# MT-PowerDivider_V1_0_0.net
KiCad netlist of a schematic drawn in Altium Designer
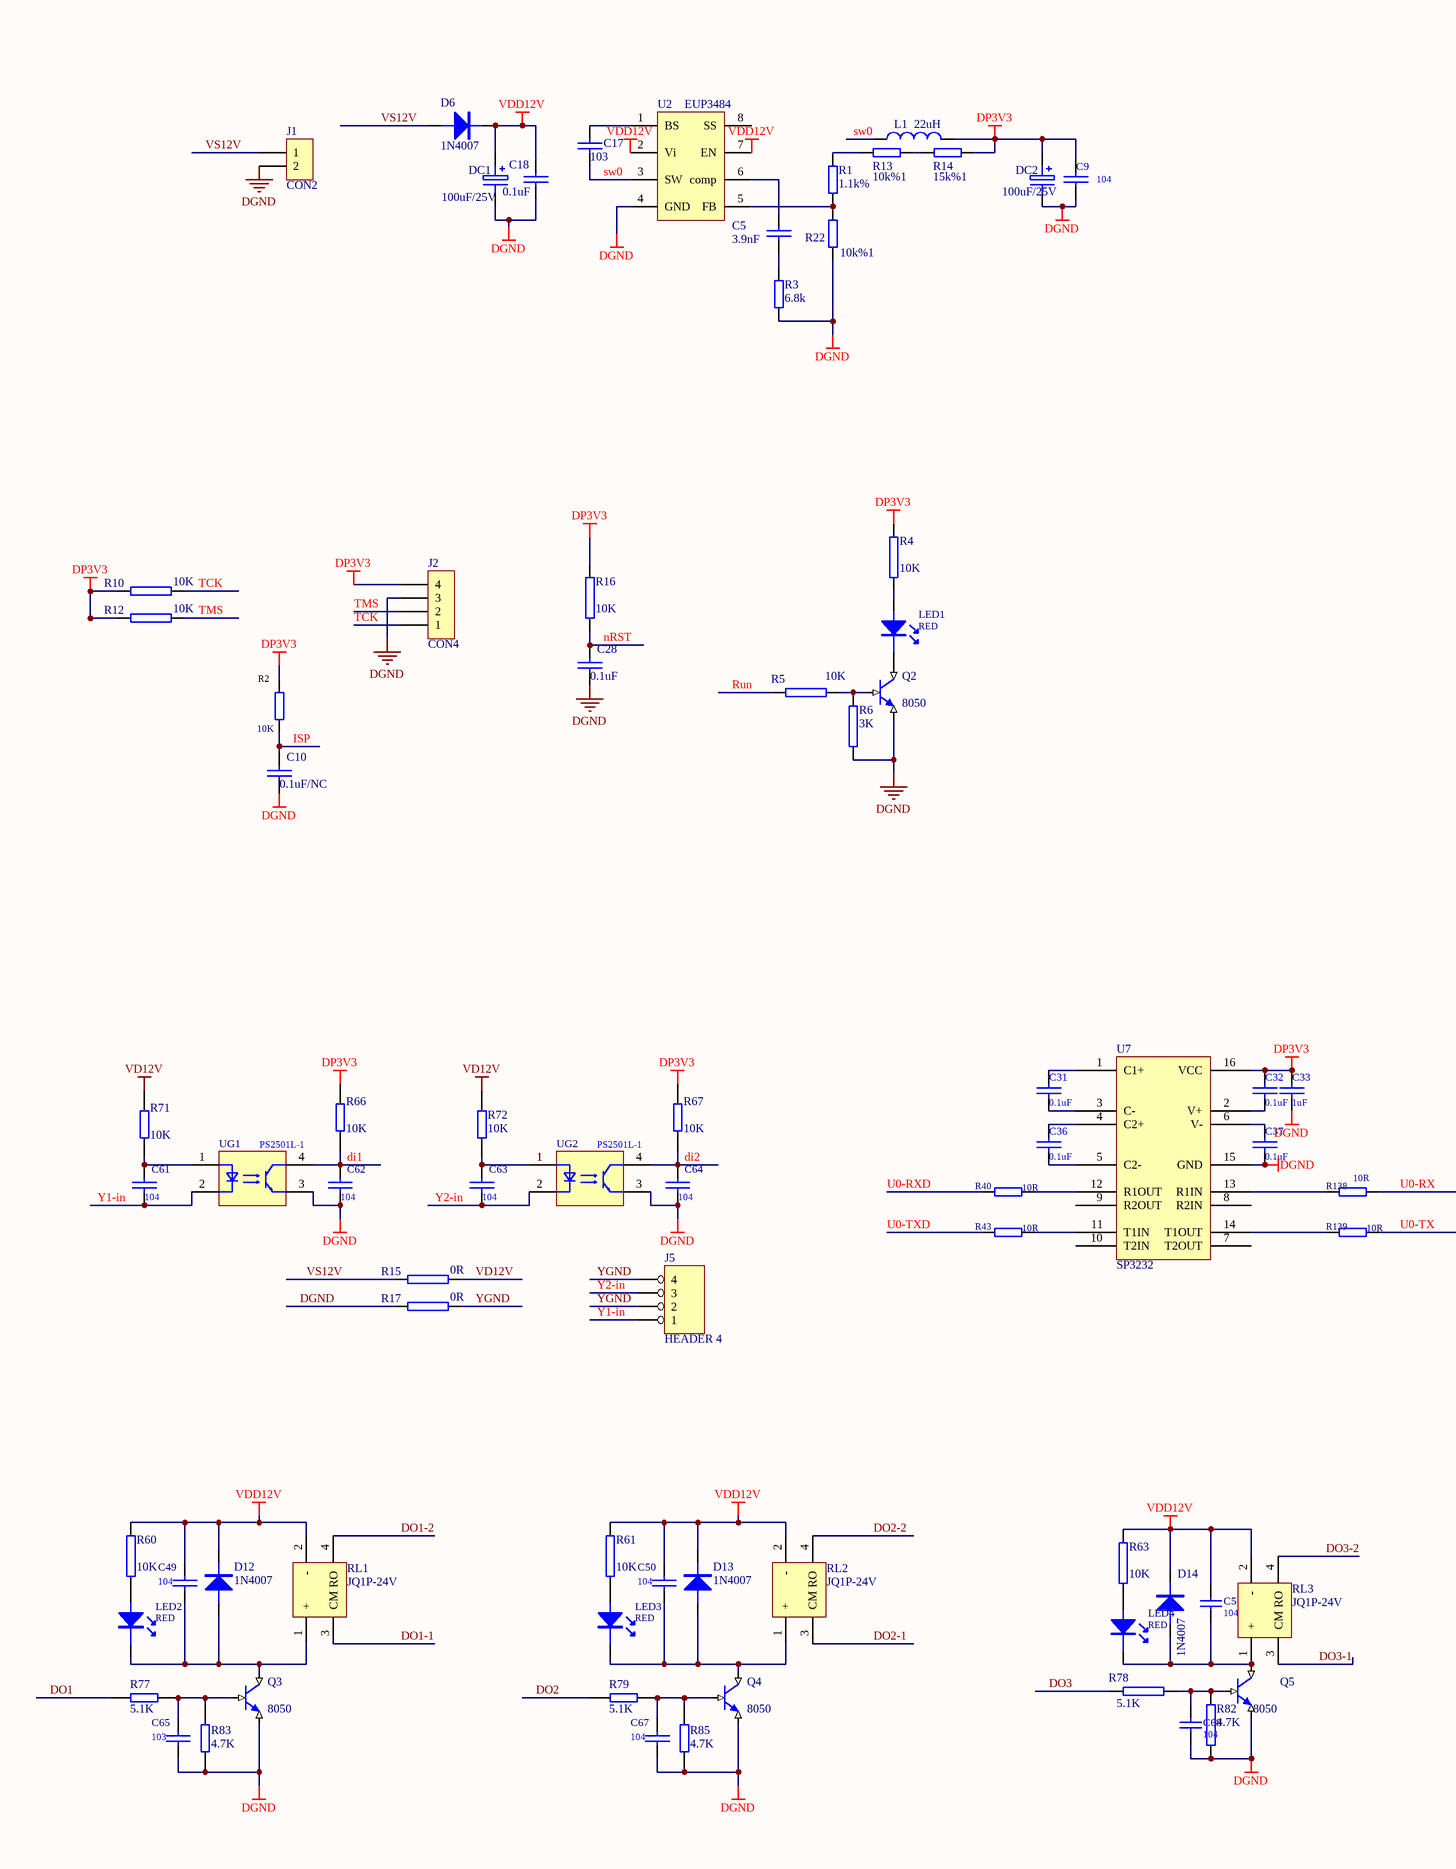
[diagram p0: MT-PowerDivider V1.0.0.SchDoc, left]
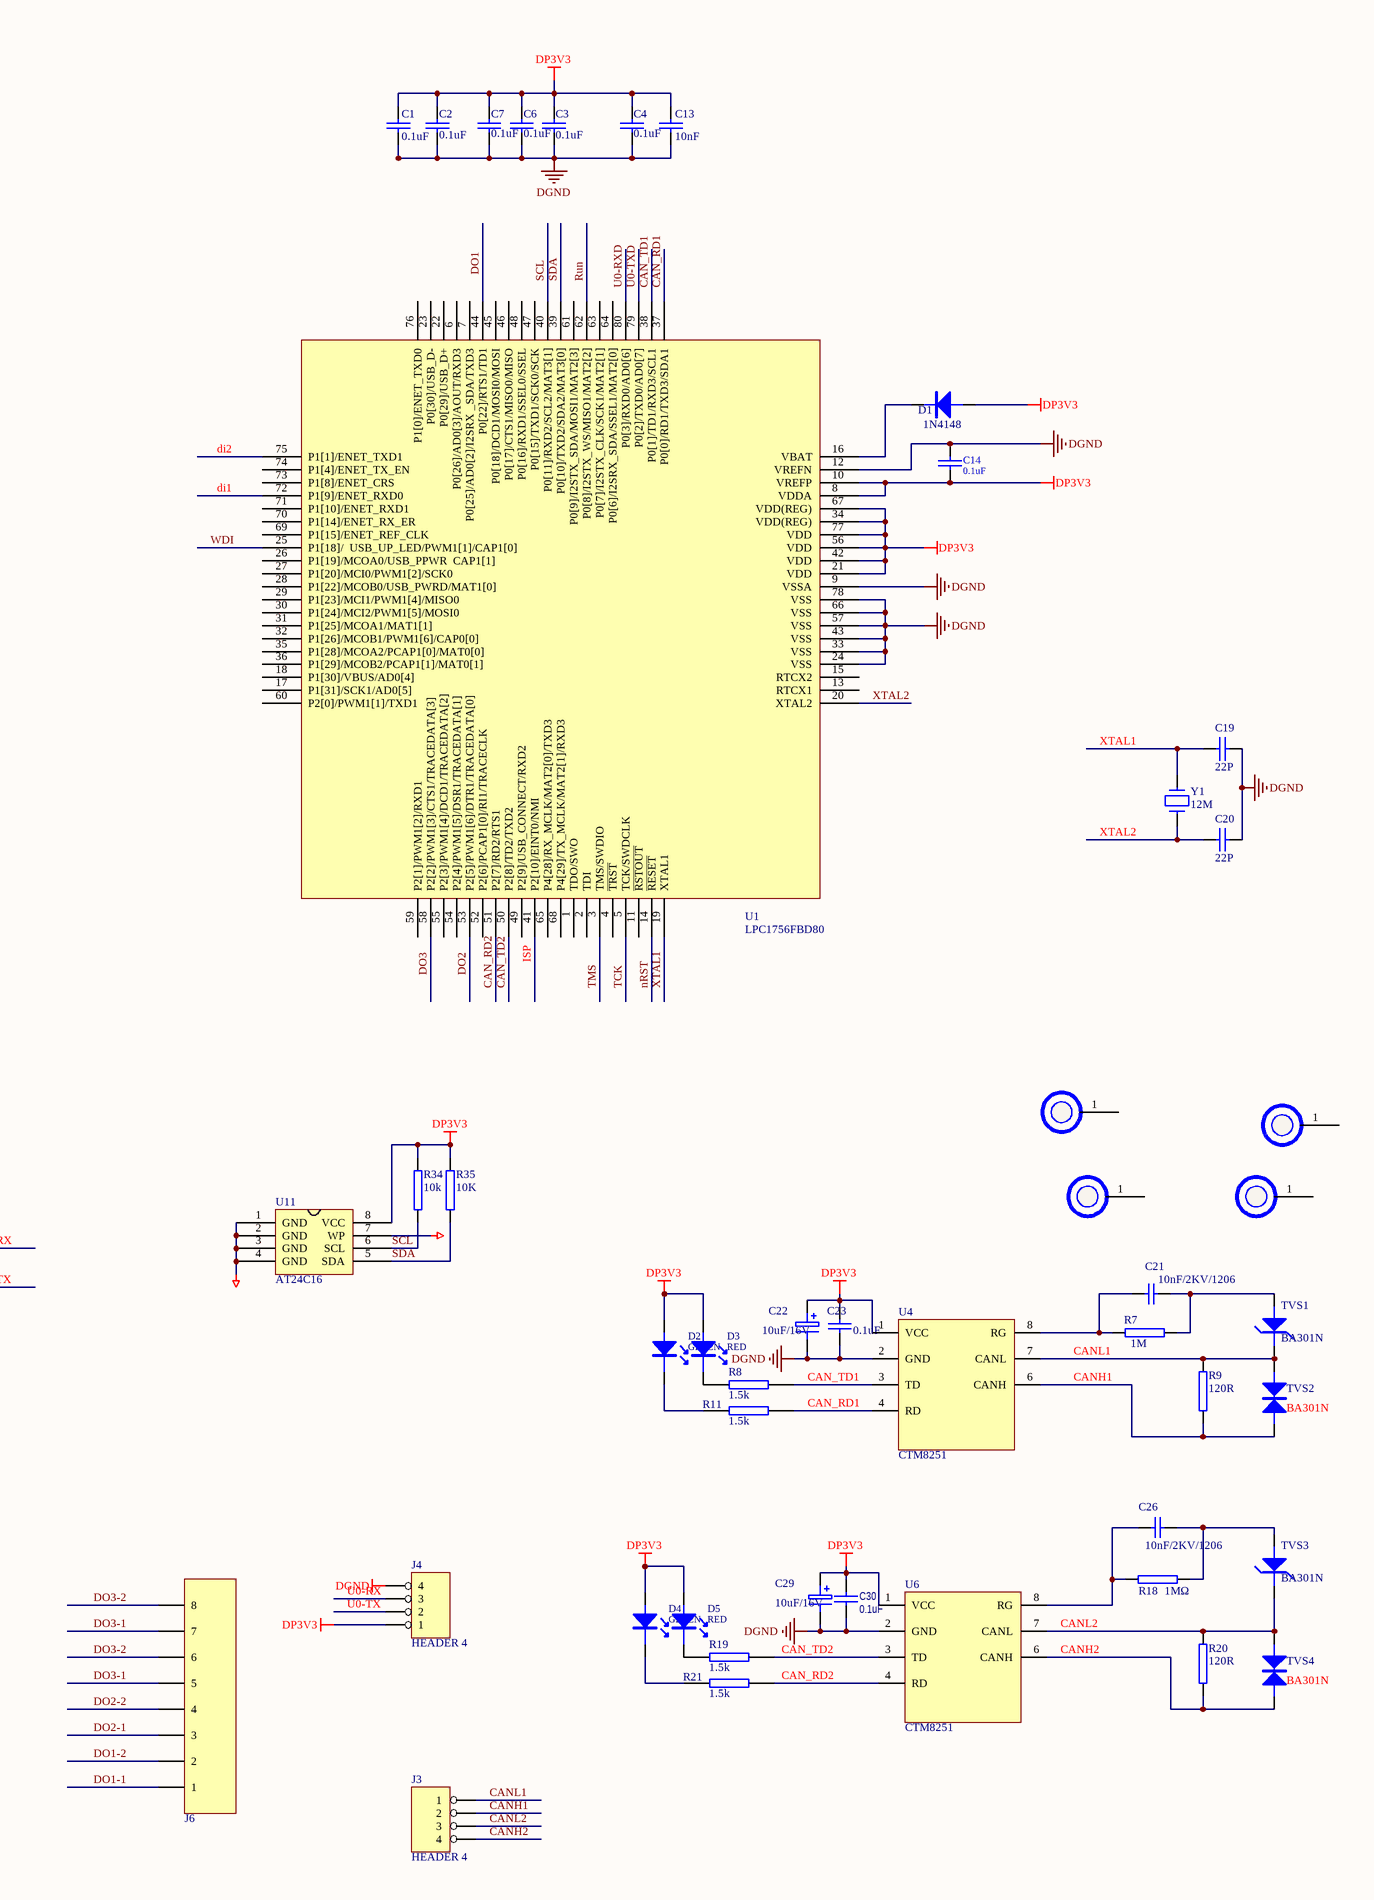
[diagram p1: MT-PowerDivider V1.0.0.SchDoc, right]

(export (version "E")
  (design (tool "Eeschema 10.0.6"))
  (components
    (comp (ref "5") (value "~") (footprint "HOLD-3.5MM") (libsource (lib "xiaodong") (part "HOLD_5X9MM")))
    (comp (ref "6") (value "~") (footprint "HOLD-3.5MM") (libsource (lib "xiaodong") (part "HOLD_5X9MM")))
    (comp (ref "7") (value "~") (footprint "HOLD-3.5MM") (libsource (lib "xiaodong") (part "HOLD_5X9MM")))
    (comp (ref "8") (value "~") (footprint "HOLD-3.5MM") (libsource (lib "xiaodong") (part "HOLD_5X9MM")))
    (comp (ref "C1") (value "0.1uF") (footprint "0603C") (libsource (lib "*") (part "CAP1")))
    (comp (ref "C2") (value "0.1uF") (footprint "0603C") (libsource (lib "*") (part "CAP1")))
    (comp (ref "C3") (value "0.1uF") (footprint "0603C") (libsource (lib "*") (part "CAP1")))
    (comp (ref "C4") (value "0.1uF") (footprint "0603C") (libsource (lib "*") (part "CAP1")))
    (comp (ref "C5") (value "3.9nF") (footprint "0603C") (libsource (lib "*") (part "CAP")))
    (comp (ref "C6") (value "0.1uF") (footprint "0603C") (libsource (lib "*") (part "CAP1")))
    (comp (ref "C7") (value "0.1uF") (footprint "0603C") (libsource (lib "*") (part "CAP1")))
    (comp (ref "C9")
      (value "104")
      (footprint "0603C")
      (description "Capacitor")
      (libsource (lib "*") (part "CAP"))
    )
    (comp (ref "C10")
      (value "0.1uF/NC")
      (footprint "0603C")
      (description "CAP")
      (libsource (lib "*") (part "CAP1"))
    )
    (comp (ref "C13") (value "10nF") (footprint "0603C") (libsource (lib "*") (part "CAP1")))
    (comp (ref "C14")
      (value "0.1uF")
      (footprint "0603C")
      (description "Capacitor")
      (libsource (lib "xiaodong") (part "CAP_3"))
    )
    (comp (ref "C17") (value "103") (footprint "0603C") (libsource (lib "*") (part "CAP")))
    (comp (ref "C18") (value "0.1uF") (footprint "0805C") (libsource (lib "*") (part "CAP")))
    (comp (ref "C19") (value "22P") (footprint "0603C") (libsource (lib "*") (part "CAP1")))
    (comp (ref "C20") (value "22P") (footprint "0603C") (libsource (lib "*") (part "CAP1")))
    (comp (ref "C21")
      (value "10nF/2KV/1206")
      (footprint "1206C")
      (description "C0603")
      (fields (field (name "PUBLISHER") "*"))
      (libsource (lib "*") (part "0.1uF"))
    )
    (comp (ref "C22") (value "10uF/16V") (footprint "CA1206") (libsource (lib "*") (part "CAP2")))
    (comp (ref "C23")
      (value "0.1uF")
      (footprint "0603C")
      (description "Capacitor")
      (libsource (lib "") (part "CAP_1"))
    )
    (comp (ref "C26")
      (value "10nF/2KV/1206")
      (footprint "1206C")
      (description "C0603")
      (fields (field (name "PUBLISHER") "*"))
      (libsource (lib "*") (part "0.1uF"))
    )
    (comp (ref "C28")
      (value "0.1uF")
      (footprint "0603C")
      (description "CAP")
      (libsource (lib "*") (part "CAP1"))
    )
    (comp (ref "C29") (value "10uF/16V") (footprint "CA1206") (libsource (lib "*") (part "CAP2")))
    (comp (ref "C30")
      (value "0.1uF")
      (footprint "0603C")
      (description "Capacitor")
      (libsource (lib "") (part "CAP_1"))
    )
    (comp (ref "C31")
      (value "0.1uF")
      (footprint "0603C")
      (description "Capacitor")
      (libsource (lib "*") (part "CAP"))
    )
    (comp (ref "C32")
      (value "0.1uF")
      (footprint "0603C")
      (description "Capacitor")
      (libsource (lib "*") (part "CAP"))
    )
    (comp (ref "C33")
      (value "1uF")
      (footprint "0603C")
      (description "Capacitor")
      (libsource (lib "*") (part "CAP"))
    )
    (comp (ref "C36")
      (value "0.1uF")
      (footprint "0603C")
      (description "Capacitor")
      (libsource (lib "*") (part "CAP"))
    )
    (comp (ref "C37")
      (value "0.1uF")
      (footprint "0603C")
      (description "Capacitor")
      (libsource (lib "*") (part "CAP"))
    )
    (comp (ref "C49")
      (value "104")
      (footprint "0603C")
      (description "Capacitor")
      (libsource (lib "*") (part "CAP"))
    )
    (comp (ref "C50")
      (value "104")
      (footprint "0603C")
      (description "Capacitor")
      (libsource (lib "*") (part "CAP"))
    )
    (comp (ref "C51")
      (value "104")
      (footprint "0603C")
      (description "Capacitor")
      (fields (field (name "PUBLISHER") "*"))
      (libsource (lib "*") (part "Cap"))
    )
    (comp (ref "C61")
      (value "104")
      (footprint "0603C")
      (description "Capacitor")
      (libsource (lib "*") (part "CAP"))
    )
    (comp (ref "C62")
      (value "104")
      (footprint "0603C")
      (description "Capacitor")
      (libsource (lib "*") (part "CAP"))
    )
    (comp (ref "C63")
      (value "104")
      (footprint "0603C")
      (description "Capacitor")
      (libsource (lib "*") (part "CAP"))
    )
    (comp (ref "C64")
      (value "104")
      (footprint "0603C")
      (description "Capacitor")
      (libsource (lib "*") (part "CAP"))
    )
    (comp (ref "C65")
      (value "103")
      (footprint "0603C")
      (description "Capacitor")
      (libsource (lib "*") (part "CAP"))
    )
    (comp (ref "C67")
      (value "104")
      (footprint "0603C")
      (description "Capacitor")
      (libsource (lib "*") (part "CAP"))
    )
    (comp (ref "C68")
      (value "104")
      (footprint "0603C")
      (description "Capacitor")
      (fields (field (name "PUBLISHER") "*"))
      (libsource (lib "*") (part "Cap"))
    )
    (comp (ref "D1") (value "1N4148") (footprint "1206D") (libsource (lib "*") (part "DIODE")))
    (comp (ref "D2") (value "GREEN") (footprint "D0805") (libsource (lib "*") (part "LED")))
    (comp (ref "D3") (value "RED") (footprint "D0805") (libsource (lib "*") (part "LED")))
    (comp (ref "D4") (value "GREEN") (footprint "D0805") (libsource (lib "*") (part "LED")))
    (comp (ref "D5") (value "RED") (footprint "D0805") (libsource (lib "*") (part "LED")))
    (comp (ref "D6") (value "1N4007") (footprint "1206D") (libsource (lib "ucharge06011415") (part "DIODE")))
    (comp (ref "D12") (value "1N4007") (footprint "1206D") (libsource (lib "*") (part "DIODE")))
    (comp (ref "D13") (value "1N4007") (footprint "1206D") (libsource (lib "*") (part "DIODE")))
    (comp (ref "D14") (value "1N4007") (footprint "1206D") (libsource (lib "*") (part "DIODE")))
    (comp (ref "DC1") (value "100uF/25V") (footprint "C100UF16VEJ") (libsource (lib "*") (part "CAP2")))
    (comp (ref "DC2") (value "100uF/25V") (footprint "C100UF16VEJ") (libsource (lib "*") (part "CAP2")))
    (comp (ref "J1")
      (value "CON2")
      (footprint "KF2EDG-2P=3.81mm")
      (libsource (lib "ucharge06011415") (part "CON2"))
    )
    (comp (ref "J2")
      (value "CON4")
      (footprint "COM4-2.54mm-90")
      (description "Connector")
      (libsource (lib "Mini9") (part "CON4"))
    )
    (comp (ref "J3")
      (value "HEADER 4")
      (footprint "KF2EDG-4P-3.81mm")
      (description "4 Pin Header")
      (libsource (lib "") (part "4 HEADER_1"))
    )
    (comp (ref "J4")
      (value "HEADER 4")
      (footprint "KF2EDG-4P-3.81mm")
      (description "4 Pin Header")
      (libsource (lib "ueee20160531") (part "4 HEADER"))
    )
    (comp (ref "J5")
      (value "HEADER 4")
      (footprint "KF2EDG-4P-3.81mm")
      (description "4 Pin Header")
      (libsource (lib "ueee20160531") (part "4 HEADER"))
    )
    (comp (ref "J6") (value "CON8") (footprint "KF2EDG-8P-3.81mm") (libsource (lib "MT") (part "CON8")))
    (comp (ref "L1") (value "22uH") (footprint "LC7*7*3_L") (libsource (lib "*") (part "INDUCTOR")))
    (comp (ref "LED1") (value "RED") (footprint "D0805") (libsource (lib "*") (part "LED")))
    (comp (ref "LED2") (value "RED") (footprint "D0805") (libsource (lib "*") (part "LED")))
    (comp (ref "LED3") (value "RED") (footprint "D0805") (libsource (lib "*") (part "LED")))
    (comp (ref "LED4") (value "RED") (footprint "D0805") (libsource (lib "*") (part "LED")))
    (comp (ref "Q2") (value "8050") (footprint "SOT23") (libsource (lib "*") (part "NPN")))
    (comp (ref "Q3") (value "8050") (footprint "SOT23") (libsource (lib "*") (part "NPN")))
    (comp (ref "Q4") (value "8050") (footprint "SOT23") (libsource (lib "*") (part "NPN")))
    (comp (ref "Q5") (value "8050") (footprint "SOT23") (libsource (lib "*") (part "NPN")))
    (comp (ref "R1") (value "1.1k%") (footprint "0603R") (libsource (lib "*") (part "R_S")))
    (comp (ref "R2")
      (value "10K")
      (footprint "0603R")
      (description "RES")
      (libsource (lib "*") (part "RES-1"))
    )
    (comp (ref "R3") (value "6.8k") (footprint "0603R") (libsource (lib "*") (part "R_S")))
    (comp (ref "R4") (value "10K") (footprint "0603R") (libsource (lib "*") (part "RES1")))
    (comp (ref "R5") (value "10K") (footprint "0603R") (libsource (lib "*") (part "RES1")))
    (comp (ref "R6") (value "3K") (footprint "0603R") (libsource (lib "*") (part "RES1")))
    (comp (ref "R7") (value "1M") (footprint "1206R") (libsource (lib "") (part "RES2_1")))
    (comp (ref "R8") (value "1.5k") (footprint "0603R") (libsource (lib "*") (part "RES2")))
    (comp (ref "R9") (value "120R") (footprint "1206R") (libsource (lib "") (part "RES2_1")))
    (comp (ref "R10") (value "10K") (footprint "0603R") (libsource (lib "*") (part "RES1")))
    (comp (ref "R11") (value "1.5k") (footprint "0603R") (libsource (lib "*") (part "RES2")))
    (comp (ref "R12") (value "10K") (footprint "0603R") (libsource (lib "*") (part "RES1")))
    (comp (ref "R13") (value "10k%1") (footprint "0603R") (libsource (lib "*") (part "R_S")))
    (comp (ref "R14") (value "15k%1") (footprint "0603R") (libsource (lib "*") (part "R_S")))
    (comp (ref "R15") (value "0R") (footprint "0603R") (libsource (lib "*") (part "RES1")))
    (comp (ref "R16") (value "10K") (footprint "0603R") (libsource (lib "*") (part "RES1")))
    (comp (ref "R17") (value "0R") (footprint "0603R") (libsource (lib "*") (part "RES1")))
    (comp (ref "R18")
      (value "1MΩ")
      (footprint "1206R")
      (fields (field (name "Comment") "1M"))
      (libsource (lib "") (part "RES2_1"))
    )
    (comp (ref "R19") (value "1.5k") (footprint "0603R") (libsource (lib "*") (part "RES2")))
    (comp (ref "R20") (value "120R") (footprint "1206R") (libsource (lib "") (part "RES2_1")))
    (comp (ref "R21") (value "1.5k") (footprint "0603R") (libsource (lib "*") (part "RES2")))
    (comp (ref "R22") (value "10k%1") (footprint "0603R") (libsource (lib "*") (part "R_S")))
    (comp (ref "R34")
      (value "10k")
      (footprint "0603R")
      (description "0603贴片电阻/10K/0.1W/±5%")
      (libsource (lib "") (part "RES1_2"))
    )
    (comp (ref "R35")
      (value "10K")
      (footprint "0603R")
      (description "0603贴片电阻/10K/0.1W/±5%")
      (libsource (lib "") (part "RES1_2"))
    )
    (comp (ref "R40")
      (value "10R")
      (footprint "0603R")
      (description "RES")
      (libsource (lib "*") (part "RES-1"))
    )
    (comp (ref "R43")
      (value "10R")
      (footprint "0603R")
      (description "RES")
      (libsource (lib "*") (part "RES-1"))
    )
    (comp (ref "R60") (value "10K") (footprint "0603R") (libsource (lib "*") (part "RES1")))
    (comp (ref "R61") (value "10K") (footprint "0603R") (libsource (lib "*") (part "RES1")))
    (comp (ref "R63") (value "10K") (footprint "0603R") (libsource (lib "*") (part "RES1")))
    (comp (ref "R66") (value "10K") (footprint "0603R") (libsource (lib "") (part "RES1_1")))
    (comp (ref "R67") (value "10K") (footprint "0603R") (libsource (lib "") (part "RES1_1")))
    (comp (ref "R71") (value "10K") (footprint "0603R") (libsource (lib "") (part "RES1_1")))
    (comp (ref "R72") (value "10K") (footprint "0603R") (libsource (lib "") (part "RES1_1")))
    (comp (ref "R77") (value "5.1K") (footprint "0603R") (libsource (lib "") (part "RES1_1")))
    (comp (ref "R78") (value "5.1K") (footprint "0603R") (libsource (lib "*") (part "RES1")))
    (comp (ref "R79") (value "5.1K") (footprint "0603R") (libsource (lib "") (part "RES1_1")))
    (comp (ref "R82") (value "4.7K") (footprint "0603R") (libsource (lib "*") (part "RES1")))
    (comp (ref "R83") (value "4.7K") (footprint "0603R") (libsource (lib "") (part "RES1_1")))
    (comp (ref "R85") (value "4.7K") (footprint "0603R") (libsource (lib "") (part "RES1_1")))
    (comp (ref "R138")
      (value "10R")
      (footprint "0603R")
      (description "RES")
      (libsource (lib "*") (part "RES-1"))
    )
    (comp (ref "R139")
      (value "10R")
      (footprint "0603R")
      (description "RES")
      (libsource (lib "*") (part "RES-1"))
    )
    (comp (ref "RL1")
      (value "JQ1P-24V")
      (footprint "HF32F-12V")
      (libsource (lib "UEEE20160408") (part "JQ1P-12V"))
    )
    (comp (ref "RL2")
      (value "JQ1P-24V")
      (footprint "HF32F-12V")
      (libsource (lib "UEEE20160408") (part "JQ1P-12V"))
    )
    (comp (ref "RL3")
      (value "JQ1P-24V")
      (footprint "HF32F-12V")
      (libsource (lib "UEEE20160408") (part "JQ1P-12V"))
    )
    (comp (ref "TVS1") (value "BA301N") (footprint "3528TVS") (libsource (lib "*") (part "TVS-D")))
    (comp (ref "TVS2") (value "BA301N") (footprint "3528TVS") (libsource (lib "*") (part "TVS")))
    (comp (ref "TVS3") (value "BA301N") (footprint "3528TVS") (libsource (lib "*") (part "TVS-D")))
    (comp (ref "TVS4") (value "BA301N") (footprint "3528TVS") (libsource (lib "*") (part "TVS")))
    (comp (ref "U1")
      (value "LPC1756FBD80")
      (footprint "LQFP-80")
      (description "LPC1756FBD80,LQFP-80_12x12x05P,NXP")
      (libsource (lib "xiaodong") (part "LPC1756FBD80"))
    )
    (comp (ref "U2") (value "EUP3484") (footprint "SOP8") (libsource (lib "*") (part "EUP3484")))
    (comp (ref "U4") (value "CTM8251") (footprint "CTM8251KT") (libsource (lib "直流原理图库") (part "CTM8251")))
    (comp (ref "U6") (value "CTM8251") (footprint "CTM8251KT") (libsource (lib "直流原理图库") (part "CTM8251")))
    (comp (ref "U7") (value "SP3232") (footprint "SO-16") (libsource (lib "*") (part "MAX232ESE")))
    (comp (ref "U11")
      (value "AT24C16")
      (footprint "SOP8")
      (description "EEPROM/64K/2.7V/SOP8/ATMEL")
      (libsource (lib "*") (part "AT24C64"))
    )
    (comp (ref "UG1") (value "PS2501L-1") (footprint "DIP-4") (libsource (lib "*") (part "PS2501-1")))
    (comp (ref "UG2") (value "PS2501L-1") (footprint "DIP-4") (libsource (lib "*") (part "PS2501-1")))
    (comp (ref "Y1") (value "12M") (footprint "ZS_SMD") (libsource (lib "*") (part "CRYSTAL")))
  )
  (nets
    (net (code "1") (name "/CANH1") (class "Default")
      (node (ref "J3") (pin "2") (pinfunction "2_2") (pintype "passive"))
      (node (ref "R9") (pin "2") (pinfunction "2_2") (pintype "passive"))
      (node (ref "TVS2") (pin "1") (pintype "passive"))
      (node (ref "U4") (pin "6") (pinfunction "CANH_6") (pintype "passive"))
    )
    (net (code "2") (name "/CANH2") (class "Default")
      (node (ref "J3") (pin "4") (pinfunction "4_4") (pintype "passive"))
      (node (ref "R20") (pin "2") (pinfunction "2_2") (pintype "passive"))
      (node (ref "TVS4") (pin "1") (pintype "passive"))
      (node (ref "U6") (pin "6") (pinfunction "CANH_6") (pintype "passive"))
    )
    (net (code "3") (name "/CANL1") (class "Default")
      (node (ref "J3") (pin "1") (pinfunction "1_1") (pintype "passive"))
      (node (ref "R9") (pin "1") (pinfunction "1_1") (pintype "passive"))
      (node (ref "TVS1") (pin "2") (pintype "passive"))
      (node (ref "TVS2") (pin "2") (pintype "passive"))
      (node (ref "U4") (pin "7") (pinfunction "CANL_7") (pintype "passive"))
    )
    (net (code "4") (name "/CANL2") (class "Default")
      (node (ref "J3") (pin "3") (pinfunction "3_3") (pintype "passive"))
      (node (ref "R20") (pin "1") (pinfunction "1_1") (pintype "passive"))
      (node (ref "TVS3") (pin "2") (pintype "passive"))
      (node (ref "TVS4") (pin "2") (pintype "passive"))
      (node (ref "U6") (pin "7") (pinfunction "CANL_7") (pintype "passive"))
    )
    (net (code "5") (name "/CAN_RD1") (class "Default")
      (node (ref "R11") (pin "2") (pinfunction "2_2") (pintype "passive"))
      (node (ref "U1") (pin "37") (pinfunction "P0[0]/RD1/TXD3/SDA1_37") (pintype "passive"))
      (node (ref "U4") (pin "4") (pinfunction "RD_4") (pintype "passive"))
    )
    (net (code "6") (name "/CAN_RD2") (class "Default")
      (node (ref "R21") (pin "2") (pinfunction "2_2") (pintype "passive"))
      (node (ref "U1") (pin "51") (pinfunction "P2[7]/RD2/RTS1_51") (pintype "passive"))
      (node (ref "U6") (pin "4") (pinfunction "RD_4") (pintype "passive"))
    )
    (net (code "7") (name "/CAN_TD1") (class "Default")
      (node (ref "R8") (pin "2") (pinfunction "2_2") (pintype "passive"))
      (node (ref "U1") (pin "38") (pinfunction "P0[1]/TD1/RXD3/SCL1_38") (pintype "passive"))
      (node (ref "U4") (pin "3") (pinfunction "TD_3") (pintype "passive"))
    )
    (net (code "8") (name "/CAN_TD2") (class "Default")
      (node (ref "R19") (pin "2") (pinfunction "2_2") (pintype "passive"))
      (node (ref "U1") (pin "50") (pinfunction "P2[8]/TD2/TXD2_50") (pintype "passive"))
      (node (ref "U6") (pin "3") (pinfunction "TD_3") (pintype "passive"))
    )
    (net (code "9") (name "/DO1") (class "Default")
      (node (ref "R77") (pin "1") (pinfunction "1_1") (pintype "passive"))
      (node (ref "U1") (pin "44") (pinfunction "P0[22]/RTS1/TD1_44") (pintype "passive"))
    )
    (net (code "10") (name "/DO1-1") (class "Default")
      (node (ref "J6") (pin "1") (pinfunction "1_1") (pintype "passive"))
      (node (ref "RL1") (pin "3") (pinfunction "CM_3") (pintype "passive"))
    )
    (net (code "11") (name "/DO1-2") (class "Default")
      (node (ref "J6") (pin "2") (pinfunction "2_2") (pintype "passive"))
      (node (ref "RL1") (pin "4") (pinfunction "RO_4") (pintype "passive"))
    )
    (net (code "12") (name "/DO2") (class "Default")
      (node (ref "R79") (pin "1") (pinfunction "1_1") (pintype "passive"))
      (node (ref "U1") (pin "53") (pinfunction "P2[5]/PWM1[6]/DTR1/TRACEDATA[0]_53") (pintype "passive"))
    )
    (net (code "13") (name "/DO2-1") (class "Default")
      (node (ref "J6") (pin "3") (pinfunction "3_3") (pintype "passive"))
      (node (ref "RL2") (pin "3") (pinfunction "CM_3") (pintype "passive"))
    )
    (net (code "14") (name "/DO2-2") (class "Default")
      (node (ref "J6") (pin "4") (pinfunction "4_4") (pintype "passive"))
      (node (ref "RL2") (pin "4") (pinfunction "RO_4") (pintype "passive"))
    )
    (net (code "15") (name "/DO3") (class "Default")
      (node (ref "R78") (pin "1") (pinfunction "1_1") (pintype "passive"))
      (node (ref "U1") (pin "58") (pinfunction "P2[2]/PWM1[3]/CTS1/TRACEDATA[3]_58") (pintype "passive"))
    )
    (net (code "16") (name "/DO3-1") (class "Default")
      (node (ref "J6") (pin "5") (pinfunction "5_5") (pintype "passive"))
      (node (ref "J6") (pin "7") (pinfunction "7_7") (pintype "passive"))
      (node (ref "RL3") (pin "3") (pinfunction "CM_3") (pintype "passive"))
    )
    (net (code "17") (name "/DO3-2") (class "Default")
      (node (ref "J6") (pin "6") (pinfunction "6_6") (pintype "passive"))
      (node (ref "J6") (pin "8") (pinfunction "8_8") (pintype "passive"))
      (node (ref "RL3") (pin "4") (pinfunction "RO_4") (pintype "passive"))
    )
    (net (code "18") (name "/ISP") (class "Default")
      (node (ref "C10") (pin "2") (pinfunction "2_2") (pintype "passive"))
      (node (ref "R2") (pin "1") (pintype "passive"))
      (node (ref "U1") (pin "41") (pinfunction "P2[10]/EINT0/NMI_41") (pintype "passive"))
    )
    (net (code "19") (name "/Run") (class "Default")
      (node (ref "R5") (pin "1") (pinfunction "1_1") (pintype "passive"))
      (node (ref "U1") (pin "62") (pinfunction "P0[8]/I2STX_WS/MISO1/MAT2[2]_62") (pintype "passive"))
    )
    (net (code "20") (name "/SCL") (class "Default")
      (node (ref "R34") (pin "2") (pinfunction "2_2") (pintype "passive"))
      (node (ref "U1") (pin "40") (pinfunction "P0[11]/RXD2/SCL2/MAT3[1]_40") (pintype "passive"))
      (node (ref "U11") (pin "6") (pinfunction "SCL_6") (pintype "passive"))
    )
    (net (code "21") (name "/SDA") (class "Default")
      (node (ref "R35") (pin "2") (pinfunction "2_2") (pintype "passive"))
      (node (ref "U1") (pin "39") (pinfunction "P0[10]/TXD2/SDA2/MAT3[0]_39") (pintype "passive"))
      (node (ref "U11") (pin "5") (pinfunction "SDA_5") (pintype "passive"))
    )
    (net (code "22") (name "/TCK") (class "Default")
      (node (ref "J2") (pin "1") (pinfunction "1_1") (pintype "passive"))
      (node (ref "R10") (pin "1") (pinfunction "1_1") (pintype "passive"))
      (node (ref "U1") (pin "5") (pinfunction "TCK/SWDCLK_5") (pintype "passive"))
    )
    (net (code "23") (name "/TMS") (class "Default")
      (node (ref "J2") (pin "2") (pinfunction "2_2") (pintype "passive"))
      (node (ref "R12") (pin "1") (pinfunction "1_1") (pintype "passive"))
      (node (ref "U1") (pin "3") (pinfunction "TMS/SWDIO_3") (pintype "passive"))
    )
    (net (code "24") (name "/U0-RX") (class "Default")
      (node (ref "J4") (pin "3") (pinfunction "3_3") (pintype "passive"))
      (node (ref "R138") (pin "2") (pintype "passive"))
    )
    (net (code "25") (name "/U0-RXD") (class "Default")
      (node (ref "R40") (pin "1") (pintype "passive"))
      (node (ref "U1") (pin "80") (pinfunction "P0[3]/RXD0/AD0[6]_80") (pintype "passive"))
    )
    (net (code "26") (name "/U0-TX") (class "Default")
      (node (ref "J4") (pin "2") (pinfunction "2_2") (pintype "passive"))
      (node (ref "R139") (pin "2") (pintype "passive"))
    )
    (net (code "27") (name "/U0-TXD") (class "Default")
      (node (ref "R43") (pin "1") (pintype "passive"))
      (node (ref "U1") (pin "79") (pinfunction "P0[2]/TXD0/AD0[7]_79") (pintype "passive"))
    )
    (net (code "28") (name "/VS12V") (class "Default")
      (node (ref "D6") (pin "1") (pinfunction "A_1") (pintype "passive"))
      (node (ref "J1") (pin "1") (pinfunction "1_1") (pintype "passive"))
      (node (ref "R15") (pin "2") (pinfunction "2_2") (pintype "passive"))
    )
    (net (code "29") (name "/WDI") (class "Default")
      (node (ref "U1") (pin "25") (pinfunction "P1[18]/__USB_UP_LED/PWM1[1]/CAP1[0]_25") (pintype "passive"))
    )
    (net (code "30") (name "/XTAL1") (class "Default")
      (node (ref "C19") (pin "1") (pinfunction "1_1") (pintype "passive"))
      (node (ref "U1") (pin "19") (pinfunction "XTAL1_19") (pintype "passive"))
      (node (ref "Y1") (pin "2") (pinfunction "2_2") (pintype "passive"))
    )
    (net (code "31") (name "/XTAL2") (class "Default")
      (node (ref "C20") (pin "1") (pinfunction "1_1") (pintype "passive"))
      (node (ref "U1") (pin "20") (pinfunction "XTAL2_20") (pintype "passive"))
      (node (ref "Y1") (pin "1") (pinfunction "1_1") (pintype "passive"))
    )
    (net (code "32") (name "/Y1-in") (class "Default")
      (node (ref "C61") (pin "2") (pintype "passive"))
      (node (ref "J5") (pin "1") (pinfunction "1_1") (pintype "passive"))
      (node (ref "UG1") (pin "2") (pintype "passive"))
    )
    (net (code "33") (name "/Y2-in") (class "Default")
      (node (ref "C63") (pin "2") (pintype "passive"))
      (node (ref "J5") (pin "3") (pinfunction "3_3") (pintype "passive"))
      (node (ref "UG2") (pin "2") (pintype "passive"))
    )
    (net (code "34") (name "/YGND") (class "Default")
      (node (ref "J5") (pin "2") (pinfunction "2_2") (pintype "passive"))
      (node (ref "J5") (pin "4") (pinfunction "4_4") (pintype "passive"))
      (node (ref "R17") (pin "1") (pinfunction "1_1") (pintype "passive"))
    )
    (net (code "35") (name "/di1") (class "Default")
      (node (ref "C62") (pin "1") (pintype "passive"))
      (node (ref "R66") (pin "2") (pinfunction "2_2") (pintype "passive"))
      (node (ref "U1") (pin "72") (pinfunction "P1[9]/ENET_RXD0_72") (pintype "passive"))
      (node (ref "UG1") (pin "4") (pintype "passive"))
    )
    (net (code "36") (name "/di2") (class "Default")
      (node (ref "C64") (pin "1") (pintype "passive"))
      (node (ref "R67") (pin "2") (pinfunction "2_2") (pintype "passive"))
      (node (ref "U1") (pin "75") (pinfunction "P1[1]/ENET_TXD1_75") (pintype "passive"))
      (node (ref "UG2") (pin "4") (pintype "passive"))
    )
    (net (code "37") (name "/nRST") (class "Default")
      (node (ref "C28") (pin "2") (pinfunction "2_2") (pintype "passive"))
      (node (ref "R16") (pin "2") (pinfunction "2_2") (pintype "passive"))
      (node (ref "U1") (pin "14") (pinfunction "~{RESET}_14") (pintype "passive"))
    )
    (net (code "38") (name "/sw0") (class "Default")
      (node (ref "C17") (pin "1") (pintype "passive"))
      (node (ref "L1") (pin "1") (pinfunction "1_1") (pintype "passive"))
      (node (ref "U2") (pin "3") (pinfunction "SW_3") (pintype "passive"))
    )
    (net (code "39") (name "DGND") (class "Default")
      (node (ref "C1") (pin "2") (pinfunction "2_2") (pintype "passive"))
      (node (ref "C10") (pin "1") (pinfunction "1_1") (pintype "passive"))
      (node (ref "C13") (pin "2") (pinfunction "2_2") (pintype "passive"))
      (node (ref "C14") (pin "1") (pintype "passive"))
      (node (ref "C18") (pin "1") (pintype "passive"))
      (node (ref "C19") (pin "2") (pinfunction "2_2") (pintype "passive"))
      (node (ref "C2") (pin "2") (pinfunction "2_2") (pintype "passive"))
      (node (ref "C20") (pin "2") (pinfunction "2_2") (pintype "passive"))
      (node (ref "C22") (pin "2") (pinfunction "2_2") (pintype "passive"))
      (node (ref "C23") (pin "2") (pinfunction "2_2") (pintype "passive"))
      (node (ref "C28") (pin "1") (pinfunction "1_1") (pintype "passive"))
      (node (ref "C29") (pin "2") (pinfunction "2_2") (pintype "passive"))
      (node (ref "C3") (pin "2") (pinfunction "2_2") (pintype "passive"))
      (node (ref "C30") (pin "1") (pinfunction "1_1") (pintype "passive"))
      (node (ref "C33") (pin "1") (pintype "passive"))
      (node (ref "C37") (pin "1") (pintype "passive"))
      (node (ref "C4") (pin "2") (pinfunction "2_2") (pintype "passive"))
      (node (ref "C6") (pin "2") (pinfunction "2_2") (pintype "passive"))
      (node (ref "C62") (pin "2") (pintype "passive"))
      (node (ref "C64") (pin "2") (pintype "passive"))
      (node (ref "C65") (pin "2") (pintype "passive"))
      (node (ref "C67") (pin "2") (pintype "passive"))
      (node (ref "C68") (pin "1") (pinfunction "1_1") (pintype "passive"))
      (node (ref "C7") (pin "2") (pinfunction "2_2") (pintype "passive"))
      (node (ref "C9") (pin "1") (pintype "passive"))
      (node (ref "DC1") (pin "2") (pinfunction "2_2") (pintype "passive"))
      (node (ref "DC2") (pin "2") (pinfunction "2_2") (pintype "passive"))
      (node (ref "J1") (pin "2") (pinfunction "2_2") (pintype "passive"))
      (node (ref "J2") (pin "3") (pinfunction "3_3") (pintype "passive"))
      (node (ref "J4") (pin "4") (pinfunction "4_4") (pintype "passive"))
      (node (ref "Q2") (pin "3") (pinfunction "E_3") (pintype "input"))
      (node (ref "Q3") (pin "3") (pinfunction "E_3") (pintype "input"))
      (node (ref "Q4") (pin "3") (pinfunction "E_3") (pintype "input"))
      (node (ref "Q5") (pin "3") (pinfunction "E_3") (pintype "input"))
      (node (ref "R17") (pin "2") (pinfunction "2_2") (pintype "passive"))
      (node (ref "R22") (pin "2") (pintype "passive"))
      (node (ref "R3") (pin "2") (pintype "passive"))
      (node (ref "R6") (pin "1") (pinfunction "1_1") (pintype "passive"))
      (node (ref "R82") (pin "1") (pinfunction "1_1") (pintype "passive"))
      (node (ref "R83") (pin "1") (pinfunction "1_1") (pintype "passive"))
      (node (ref "R85") (pin "1") (pinfunction "1_1") (pintype "passive"))
      (node (ref "U1") (pin "12") (pinfunction "VREFN_12") (pintype "passive"))
      (node (ref "U1") (pin "24") (pinfunction "VSS_24") (pintype "passive"))
      (node (ref "U1") (pin "33") (pinfunction "VSS_33") (pintype "passive"))
      (node (ref "U1") (pin "43") (pinfunction "VSS_43") (pintype "passive"))
      (node (ref "U1") (pin "57") (pinfunction "VSS_57") (pintype "passive"))
      (node (ref "U1") (pin "66") (pinfunction "VSS_66") (pintype "passive"))
      (node (ref "U1") (pin "78") (pinfunction "VSS_78") (pintype "passive"))
      (node (ref "U1") (pin "9") (pinfunction "VSSA_9") (pintype "passive"))
      (node (ref "U11") (pin "1") (pinfunction "GND_1") (pintype "passive"))
      (node (ref "U11") (pin "2") (pinfunction "GND_2") (pintype "passive"))
      (node (ref "U11") (pin "3") (pinfunction "GND_3") (pintype "passive"))
      (node (ref "U11") (pin "4") (pinfunction "GND_4") (pintype "passive"))
      (node (ref "U11") (pin "7") (pinfunction "WP_7") (pintype "passive"))
      (node (ref "U2") (pin "4") (pinfunction "GND_4") (pintype "passive"))
      (node (ref "U4") (pin "2") (pinfunction "GND_2") (pintype "passive"))
      (node (ref "U6") (pin "2") (pinfunction "GND_2") (pintype "passive"))
      (node (ref "U7") (pin "15") (pinfunction "GND_15") (pintype "passive"))
      (node (ref "UG1") (pin "3") (pintype "passive"))
      (node (ref "UG2") (pin "3") (pintype "passive"))
    )
    (net (code "40") (name "DP3V3") (class "Default")
      (node (ref "C1") (pin "1") (pinfunction "1_1") (pintype "passive"))
      (node (ref "C13") (pin "1") (pinfunction "1_1") (pintype "passive"))
      (node (ref "C14") (pin "2") (pintype "passive"))
      (node (ref "C2") (pin "1") (pinfunction "1_1") (pintype "passive"))
      (node (ref "C22") (pin "1") (pinfunction "1_1") (pintype "passive"))
      (node (ref "C23") (pin "1") (pinfunction "1_1") (pintype "passive"))
      (node (ref "C29") (pin "1") (pinfunction "1_1") (pintype "passive"))
      (node (ref "C3") (pin "1") (pinfunction "1_1") (pintype "passive"))
      (node (ref "C30") (pin "2") (pinfunction "2_2") (pintype "passive"))
      (node (ref "C32") (pin "2") (pintype "passive"))
      (node (ref "C33") (pin "2") (pintype "passive"))
      (node (ref "C4") (pin "1") (pinfunction "1_1") (pintype "passive"))
      (node (ref "C6") (pin "1") (pinfunction "1_1") (pintype "passive"))
      (node (ref "C7") (pin "1") (pinfunction "1_1") (pintype "passive"))
      (node (ref "C9") (pin "2") (pintype "passive"))
      (node (ref "D1") (pin "1") (pinfunction "A_1") (pintype "passive"))
      (node (ref "D2") (pin "1") (pintype "passive"))
      (node (ref "D3") (pin "1") (pintype "passive"))
      (node (ref "D4") (pin "1") (pintype "passive"))
      (node (ref "D5") (pin "1") (pintype "passive"))
      (node (ref "DC2") (pin "1") (pinfunction "1_1") (pintype "passive"))
      (node (ref "J2") (pin "4") (pinfunction "4_4") (pintype "passive"))
      (node (ref "J4") (pin "1") (pinfunction "1_1") (pintype "passive"))
      (node (ref "L1") (pin "2") (pinfunction "2_2") (pintype "passive"))
      (node (ref "R10") (pin "2") (pinfunction "2_2") (pintype "passive"))
      (node (ref "R12") (pin "2") (pinfunction "2_2") (pintype "passive"))
      (node (ref "R14") (pin "1") (pintype "passive"))
      (node (ref "R16") (pin "1") (pinfunction "1_1") (pintype "passive"))
      (node (ref "R2") (pin "2") (pintype "passive"))
      (node (ref "R34") (pin "1") (pinfunction "1_1") (pintype "passive"))
      (node (ref "R35") (pin "1") (pinfunction "1_1") (pintype "passive"))
      (node (ref "R4") (pin "2") (pinfunction "2_2") (pintype "passive"))
      (node (ref "R66") (pin "1") (pinfunction "1_1") (pintype "passive"))
      (node (ref "R67") (pin "1") (pinfunction "1_1") (pintype "passive"))
      (node (ref "U1") (pin "10") (pinfunction "VREFP_10") (pintype "passive"))
      (node (ref "U1") (pin "21") (pinfunction "VDD_21") (pintype "passive"))
      (node (ref "U1") (pin "34") (pinfunction "VDD(REG)_34") (pintype "passive"))
      (node (ref "U1") (pin "42") (pinfunction "VDD_42") (pintype "passive"))
      (node (ref "U1") (pin "56") (pinfunction "VDD_56") (pintype "passive"))
      (node (ref "U1") (pin "67") (pinfunction "VDD(REG)_67") (pintype "passive"))
      (node (ref "U1") (pin "77") (pinfunction "VDD_77") (pintype "passive"))
      (node (ref "U1") (pin "8") (pinfunction "VDDA_8") (pintype "passive"))
      (node (ref "U11") (pin "8") (pinfunction "VCC_8") (pintype "passive"))
      (node (ref "U4") (pin "1") (pinfunction "VCC_1") (pintype "passive"))
      (node (ref "U6") (pin "1") (pinfunction "VCC_1") (pintype "passive"))
      (node (ref "U7") (pin "16") (pinfunction "VCC_16") (pintype "passive"))
    )
    (net (code "41") (name "Net-(C5-Pad2)") (class "Default")
      (node (ref "C5") (pin "2") (pintype "passive"))
      (node (ref "R3") (pin "1") (pintype "passive"))
    )
    (net (code "42") (name "Net-(C21-Pad1)") (class "Default")
      (node (ref "C21") (pin "1") (pinfunction "1_1") (pintype "passive"))
      (node (ref "R7") (pin "1") (pinfunction "1_1") (pintype "passive"))
      (node (ref "TVS1") (pin "1") (pintype "passive"))
    )
    (net (code "43") (name "Net-(C26-Pad2)") (class "Default")
      (node (ref "C26") (pin "2") (pinfunction "2_2") (pintype "passive"))
      (node (ref "R18") (pin "2") (pinfunction "2_2") (pintype "passive"))
      (node (ref "TVS3") (pin "1") (pintype "passive"))
    )
    (net (code "44") (name "Net-(C61-Pad1)") (class "Default")
      (node (ref "C61") (pin "1") (pintype "passive"))
      (node (ref "R71") (pin "2") (pinfunction "2_2") (pintype "passive"))
      (node (ref "UG1") (pin "1") (pintype "passive"))
    )
    (net (code "45") (name "Net-(C63-Pad1)") (class "Default")
      (node (ref "C63") (pin "1") (pintype "passive"))
      (node (ref "R72") (pin "2") (pinfunction "2_2") (pintype "passive"))
      (node (ref "UG2") (pin "1") (pintype "passive"))
    )
    (net (code "46") (name "Net-(D1-K)") (class "Default")
      (node (ref "D1") (pin "2") (pinfunction "K_2") (pintype "passive"))
      (node (ref "U1") (pin "16") (pinfunction "VBAT_16") (pintype "passive"))
    )
    (net (code "47") (name "Net-(D2-Pad2)") (class "Default")
      (node (ref "D2") (pin "2") (pintype "passive"))
      (node (ref "R11") (pin "1") (pinfunction "1_1") (pintype "passive"))
    )
    (net (code "48") (name "Net-(D3-Pad2)") (class "Default")
      (node (ref "D3") (pin "2") (pintype "passive"))
      (node (ref "R8") (pin "1") (pinfunction "1_1") (pintype "passive"))
    )
    (net (code "49") (name "Net-(D4-Pad2)") (class "Default")
      (node (ref "D4") (pin "2") (pintype "passive"))
      (node (ref "R21") (pin "1") (pinfunction "1_1") (pintype "passive"))
    )
    (net (code "50") (name "Net-(D5-Pad2)") (class "Default")
      (node (ref "D5") (pin "2") (pintype "passive"))
      (node (ref "R19") (pin "1") (pinfunction "1_1") (pintype "passive"))
    )
    (net (code "51") (name "Net-(D12-A)") (class "Default")
      (node (ref "C49") (pin "2") (pintype "passive"))
      (node (ref "D12") (pin "1") (pinfunction "A_1") (pintype "passive"))
      (node (ref "LED2") (pin "2") (pintype "passive"))
      (node (ref "Q3") (pin "2") (pinfunction "C_2") (pintype "input"))
      (node (ref "RL1") (pin "1") (pinfunction "+_1") (pintype "passive"))
    )
    (net (code "52") (name "Net-(D13-A)") (class "Default")
      (node (ref "C50") (pin "2") (pintype "passive"))
      (node (ref "D13") (pin "1") (pinfunction "A_1") (pintype "passive"))
      (node (ref "LED3") (pin "2") (pintype "passive"))
      (node (ref "Q4") (pin "2") (pinfunction "C_2") (pintype "input"))
      (node (ref "RL2") (pin "1") (pinfunction "+_1") (pintype "passive"))
    )
    (net (code "53") (name "Net-(D14-A)") (class "Default")
      (node (ref "C51") (pin "1") (pinfunction "1_1") (pintype "passive"))
      (node (ref "D14") (pin "1") (pinfunction "A_1") (pintype "passive"))
      (node (ref "LED4") (pin "2") (pintype "passive"))
      (node (ref "Q5") (pin "2") (pinfunction "C_2") (pintype "input"))
      (node (ref "RL3") (pin "1") (pinfunction "+_1") (pintype "passive"))
    )
    (net (code "54") (name "Net-(LED1-Pad1)") (class "Default")
      (node (ref "LED1") (pin "1") (pintype "passive"))
      (node (ref "R4") (pin "1") (pinfunction "1_1") (pintype "passive"))
    )
    (net (code "55") (name "Net-(LED2-Pad1)") (class "Default")
      (node (ref "LED2") (pin "1") (pintype "passive"))
      (node (ref "R60") (pin "1") (pinfunction "1_1") (pintype "passive"))
    )
    (net (code "56") (name "Net-(LED3-Pad1)") (class "Default")
      (node (ref "LED3") (pin "1") (pintype "passive"))
      (node (ref "R61") (pin "1") (pinfunction "1_1") (pintype "passive"))
    )
    (net (code "57") (name "Net-(LED4-Pad1)") (class "Default")
      (node (ref "LED4") (pin "1") (pintype "passive"))
      (node (ref "R63") (pin "1") (pinfunction "1_1") (pintype "passive"))
    )
    (net (code "58") (name "Net-(Q2-B)") (class "Default")
      (node (ref "Q2") (pin "1") (pinfunction "B_1") (pintype "input"))
      (node (ref "R5") (pin "2") (pinfunction "2_2") (pintype "passive"))
      (node (ref "R6") (pin "2") (pinfunction "2_2") (pintype "passive"))
    )
    (net (code "59") (name "Net-(Q2-C)") (class "Default")
      (node (ref "LED1") (pin "2") (pintype "passive"))
      (node (ref "Q2") (pin "2") (pinfunction "C_2") (pintype "input"))
    )
    (net (code "60") (name "Net-(Q3-B)") (class "Default")
      (node (ref "C65") (pin "1") (pintype "passive"))
      (node (ref "Q3") (pin "1") (pinfunction "B_1") (pintype "input"))
      (node (ref "R77") (pin "2") (pinfunction "2_2") (pintype "passive"))
      (node (ref "R83") (pin "2") (pinfunction "2_2") (pintype "passive"))
    )
    (net (code "61") (name "Net-(Q4-B)") (class "Default")
      (node (ref "C67") (pin "1") (pintype "passive"))
      (node (ref "Q4") (pin "1") (pinfunction "B_1") (pintype "input"))
      (node (ref "R79") (pin "2") (pinfunction "2_2") (pintype "passive"))
      (node (ref "R85") (pin "2") (pinfunction "2_2") (pintype "passive"))
    )
    (net (code "62") (name "Net-(Q5-B)") (class "Default")
      (node (ref "C68") (pin "2") (pinfunction "2_2") (pintype "passive"))
      (node (ref "Q5") (pin "1") (pinfunction "B_1") (pintype "input"))
      (node (ref "R78") (pin "2") (pinfunction "2_2") (pintype "passive"))
      (node (ref "R82") (pin "2") (pinfunction "2_2") (pintype "passive"))
    )
    (net (code "63") (name "Net-(R1-Pad1)") (class "Default")
      (node (ref "R1") (pin "1") (pintype "passive"))
      (node (ref "R13") (pin "2") (pintype "passive"))
    )
    (net (code "64") (name "Net-(R13-Pad1)") (class "Default")
      (node (ref "R13") (pin "1") (pintype "passive"))
      (node (ref "R14") (pin "2") (pintype "passive"))
    )
    (net (code "65") (name "Net-(U2-BS)") (class "Default")
      (node (ref "C17") (pin "2") (pintype "passive"))
      (node (ref "U2") (pin "1") (pinfunction "BS_1") (pintype "passive"))
    )
    (net (code "66") (name "Net-(U2-FB)") (class "Default")
      (node (ref "R1") (pin "2") (pintype "passive"))
      (node (ref "R22") (pin "1") (pintype "passive"))
      (node (ref "U2") (pin "5") (pinfunction "FB_5") (pintype "passive"))
    )
    (net (code "67") (name "Net-(U2-comp)") (class "Default")
      (node (ref "C5") (pin "1") (pintype "passive"))
      (node (ref "U2") (pin "6") (pinfunction "comp_6") (pintype "passive"))
    )
    (net (code "68") (name "Net-(U4-RG)") (class "Default")
      (node (ref "C21") (pin "2") (pinfunction "2_2") (pintype "passive"))
      (node (ref "R7") (pin "2") (pinfunction "2_2") (pintype "passive"))
      (node (ref "U4") (pin "8") (pinfunction "RG_8") (pintype "passive"))
    )
    (net (code "69") (name "Net-(U6-RG)") (class "Default")
      (node (ref "C26") (pin "1") (pinfunction "1_1") (pintype "passive"))
      (node (ref "R18") (pin "1") (pinfunction "1_1") (pintype "passive"))
      (node (ref "U6") (pin "8") (pinfunction "RG_8") (pintype "passive"))
    )
    (net (code "70") (name "Net-(U7-C-)") (class "Default")
      (node (ref "C31") (pin "1") (pintype "passive"))
      (node (ref "U7") (pin "3") (pinfunction "C-_3") (pintype "passive"))
    )
    (net (code "71") (name "Net-(U7-C1+)") (class "Default")
      (node (ref "C31") (pin "2") (pintype "passive"))
      (node (ref "U7") (pin "1") (pinfunction "C1+_1") (pintype "passive"))
    )
    (net (code "72") (name "Net-(U7-C2+)") (class "Default")
      (node (ref "C36") (pin "2") (pintype "passive"))
      (node (ref "U7") (pin "4") (pinfunction "C2+_4") (pintype "passive"))
    )
    (net (code "73") (name "Net-(U7-C2-)") (class "Default")
      (node (ref "C36") (pin "1") (pintype "passive"))
      (node (ref "U7") (pin "5") (pinfunction "C2-_5") (pintype "passive"))
    )
    (net (code "74") (name "Net-(U7-R1IN)") (class "Default")
      (node (ref "R138") (pin "1") (pintype "passive"))
      (node (ref "U7") (pin "13") (pinfunction "R1IN_13") (pintype "passive"))
    )
    (net (code "75") (name "Net-(U7-R1OUT)") (class "Default")
      (node (ref "R40") (pin "2") (pintype "passive"))
      (node (ref "U7") (pin "12") (pinfunction "R1OUT_12") (pintype "passive"))
    )
    (net (code "76") (name "Net-(U7-T1IN)") (class "Default")
      (node (ref "R43") (pin "2") (pintype "passive"))
      (node (ref "U7") (pin "11") (pinfunction "T1IN_11") (pintype "passive"))
    )
    (net (code "77") (name "Net-(U7-T1OUT)") (class "Default")
      (node (ref "R139") (pin "1") (pintype "passive"))
      (node (ref "U7") (pin "14") (pinfunction "T1OUT_14") (pintype "passive"))
    )
    (net (code "78") (name "Net-(U7-V+)") (class "Default")
      (node (ref "C32") (pin "1") (pintype "passive"))
      (node (ref "U7") (pin "2") (pinfunction "V+_2") (pintype "passive"))
    )
    (net (code "79") (name "Net-(U7-V-)") (class "Default")
      (node (ref "C37") (pin "2") (pintype "passive"))
      (node (ref "U7") (pin "6") (pinfunction "V-_6") (pintype "passive"))
    )
    (net (code "80") (name "VD12V") (class "Default")
      (node (ref "R15") (pin "1") (pinfunction "1_1") (pintype "passive"))
      (node (ref "R71") (pin "1") (pinfunction "1_1") (pintype "passive"))
      (node (ref "R72") (pin "1") (pinfunction "1_1") (pintype "passive"))
    )
    (net (code "81") (name "VDD12V") (class "Default")
      (node (ref "C18") (pin "2") (pintype "passive"))
      (node (ref "C49") (pin "1") (pintype "passive"))
      (node (ref "C50") (pin "1") (pintype "passive"))
      (node (ref "C51") (pin "2") (pinfunction "2_2") (pintype "passive"))
      (node (ref "D12") (pin "2") (pinfunction "K_2") (pintype "passive"))
      (node (ref "D13") (pin "2") (pinfunction "K_2") (pintype "passive"))
      (node (ref "D14") (pin "2") (pinfunction "K_2") (pintype "passive"))
      (node (ref "D6") (pin "2") (pinfunction "K_2") (pintype "passive"))
      (node (ref "DC1") (pin "1") (pinfunction "1_1") (pintype "passive"))
      (node (ref "R60") (pin "2") (pinfunction "2_2") (pintype "passive"))
      (node (ref "R61") (pin "2") (pinfunction "2_2") (pintype "passive"))
      (node (ref "R63") (pin "2") (pinfunction "2_2") (pintype "passive"))
      (node (ref "RL1") (pin "2") (pinfunction "-_2") (pintype "passive"))
      (node (ref "RL2") (pin "2") (pinfunction "-_2") (pintype "passive"))
      (node (ref "RL3") (pin "2") (pinfunction "-_2") (pintype "passive"))
      (node (ref "U2") (pin "2") (pinfunction "Vi_2") (pintype "passive"))
      (node (ref "U2") (pin "7") (pinfunction "EN_7") (pintype "passive"))
    )
    (net (code "82") (name "unconnected-(5-HOLD-Pad1)") (class "Default")
      (node (ref "5") (pin "1") (pinfunction "HOLD_1") (pintype "passive"))
    )
    (net (code "83") (name "unconnected-(6-HOLD-Pad1)") (class "Default")
      (node (ref "6") (pin "1") (pinfunction "HOLD_1") (pintype "passive"))
    )
    (net (code "84") (name "unconnected-(7-HOLD-Pad1)") (class "Default")
      (node (ref "7") (pin "1") (pinfunction "HOLD_1") (pintype "passive"))
    )
    (net (code "85") (name "unconnected-(8-HOLD-Pad1)") (class "Default")
      (node (ref "8") (pin "1") (pinfunction "HOLD_1") (pintype "passive"))
    )
    (net (code "86") (name "unconnected-(U1-P0[6]{slash}I2SRX_SDA{slash}SSEL1{slash}MAT2[0]-Pad64)") (class "Default")
      (node (ref "U1") (pin "64") (pinfunction "P0[6]/I2SRX_SDA/SSEL1/MAT2[0]_64") (pintype "passive"))
    )
    (net (code "87") (name "unconnected-(U1-P0[7]{slash}I2STX_CLK{slash}SCK1{slash}MAT2[1]-Pad63)") (class "Default")
      (node (ref "U1") (pin "63") (pinfunction "P0[7]/I2STX_CLK/SCK1/MAT2[1]_63") (pintype "passive"))
    )
    (net (code "88") (name "unconnected-(U1-P0[9]{slash}I2STX_SDA{slash}MOSI1{slash}MAT2[3]-Pad61)") (class "Default")
      (node (ref "U1") (pin "61") (pinfunction "P0[9]/I2STX_SDA/MOSI1/MAT2[3]_61") (pintype "passive"))
    )
    (net (code "89") (name "unconnected-(U1-P0[15]{slash}TXD1{slash}SCK0{slash}SCK-Pad47)") (class "Default")
      (node (ref "U1") (pin "47") (pinfunction "P0[15]/TXD1/SCK0/SCK_47") (pintype "passive"))
    )
    (net (code "90") (name "unconnected-(U1-P0[16]{slash}RXD1{slash}SSEL0{slash}SSEL-Pad48)") (class "Default")
      (node (ref "U1") (pin "48") (pinfunction "P0[16]/RXD1/SSEL0/SSEL_48") (pintype "passive"))
    )
    (net (code "91") (name "unconnected-(U1-P0[17]{slash}CTS1{slash}MISO0{slash}MISO-Pad46)") (class "Default")
      (node (ref "U1") (pin "46") (pinfunction "P0[17]/CTS1/MISO0/MISO_46") (pintype "passive"))
    )
    (net (code "92") (name "unconnected-(U1-P0[18]{slash}DCD1{slash}MOSI0{slash}MOSI-Pad45)") (class "Default")
      (node (ref "U1") (pin "45") (pinfunction "P0[18]/DCD1/MOSI0/MOSI_45") (pintype "passive"))
    )
    (net (code "93") (name "unconnected-(U1-P0[25]{slash}AD0[2]{slash}I2SRX__SDA{slash}TXD3-Pad7)") (class "Default")
      (node (ref "U1") (pin "7") (pinfunction "P0[25]/AD0[2]/I2SRX__SDA/TXD3_7") (pintype "passive"))
    )
    (net (code "94") (name "unconnected-(U1-P0[26]{slash}AD0[3]{slash}AOUT{slash}RXD3-Pad6)") (class "Default")
      (node (ref "U1") (pin "6") (pinfunction "P0[26]/AD0[3]/AOUT/RXD3_6") (pintype "passive"))
    )
    (net (code "95") (name "unconnected-(U1-P0[29]{slash}USB_D+-Pad22)") (class "Default")
      (node (ref "U1") (pin "22") (pinfunction "P0[29]/USB_D+_22") (pintype "passive"))
    )
    (net (code "96") (name "unconnected-(U1-P0[30]{slash}USB_D--Pad23)") (class "Default")
      (node (ref "U1") (pin "23") (pinfunction "P0[30]/USB_D-_23") (pintype "passive"))
    )
    (net (code "97") (name "unconnected-(U1-P1[0]{slash}ENET_TXD0-Pad76)") (class "Default")
      (node (ref "U1") (pin "76") (pinfunction "P1[0]/ENET_TXD0_76") (pintype "passive"))
    )
    (net (code "98") (name "unconnected-(U1-P1[4]{slash}ENET_TX_EN-Pad74)") (class "Default")
      (node (ref "U1") (pin "74") (pinfunction "P1[4]/ENET_TX_EN_74") (pintype "passive"))
    )
    (net (code "99") (name "unconnected-(U1-P1[8]{slash}ENET_CRS-Pad73)") (class "Default")
      (node (ref "U1") (pin "73") (pinfunction "P1[8]/ENET_CRS_73") (pintype "passive"))
    )
    (net (code "100") (name "unconnected-(U1-P1[10]{slash}ENET_RXD1-Pad71)") (class "Default")
      (node (ref "U1") (pin "71") (pinfunction "P1[10]/ENET_RXD1_71") (pintype "passive"))
    )
    (net (code "101") (name "unconnected-(U1-P1[14]{slash}ENET_RX_ER-Pad70)") (class "Default")
      (node (ref "U1") (pin "70") (pinfunction "P1[14]/ENET_RX_ER_70") (pintype "passive"))
    )
    (net (code "102") (name "unconnected-(U1-P1[15]{slash}ENET_REF_CLK-Pad69)") (class "Default")
      (node (ref "U1") (pin "69") (pinfunction "P1[15]/ENET_REF_CLK_69") (pintype "passive"))
    )
    (net (code "103") (name "unconnected-(U1-P1[19]{slash}MCOA0{slash}USB_PPWR__CAP1[1]-Pad26)") (class "Default")
      (node (ref "U1") (pin "26") (pinfunction "P1[19]/MCOA0/USB_PPWR__CAP1[1]_26") (pintype "passive"))
    )
    (net (code "104") (name "unconnected-(U1-P1[20]{slash}MCI0{slash}PWM1[2]{slash}SCK0-Pad27)") (class "Default")
      (node (ref "U1") (pin "27") (pinfunction "P1[20]/MCI0/PWM1[2]/SCK0_27") (pintype "passive"))
    )
    (net (code "105") (name "unconnected-(U1-P1[22]{slash}MCOB0{slash}USB_PWRD{slash}MAT1[0]-Pad28)") (class "Default")
      (node (ref "U1") (pin "28") (pinfunction "P1[22]/MCOB0/USB_PWRD/MAT1[0]_28") (pintype "passive"))
    )
    (net (code "106") (name "unconnected-(U1-P1[23]{slash}MCI1{slash}PWM1[4]{slash}MISO0-Pad29)") (class "Default")
      (node (ref "U1") (pin "29") (pinfunction "P1[23]/MCI1/PWM1[4]/MISO0_29") (pintype "passive"))
    )
    (net (code "107") (name "unconnected-(U1-P1[24]{slash}MCI2{slash}PWM1[5]{slash}MOSI0-Pad30)") (class "Default")
      (node (ref "U1") (pin "30") (pinfunction "P1[24]/MCI2/PWM1[5]/MOSI0_30") (pintype "passive"))
    )
    (net (code "108") (name "unconnected-(U1-P1[25]{slash}MCOA1{slash}MAT1[1]-Pad31)") (class "Default")
      (node (ref "U1") (pin "31") (pinfunction "P1[25]/MCOA1/MAT1[1]_31") (pintype "passive"))
    )
    (net (code "109") (name "unconnected-(U1-P1[26]{slash}MCOB1{slash}PWM1[6]{slash}CAP0[0]-Pad32)") (class "Default")
      (node (ref "U1") (pin "32") (pinfunction "P1[26]/MCOB1/PWM1[6]/CAP0[0]_32") (pintype "passive"))
    )
    (net (code "110") (name "unconnected-(U1-P1[28]{slash}MCOA2{slash}PCAP1[0]{slash}MAT0[0]-Pad35)") (class "Default")
      (node (ref "U1") (pin "35") (pinfunction "P1[28]/MCOA2/PCAP1[0]/MAT0[0]_35") (pintype "passive"))
    )
    (net (code "111") (name "unconnected-(U1-P1[29]{slash}MCOB2{slash}PCAP1[1]{slash}MAT0[1]-Pad36)") (class "Default")
      (node (ref "U1") (pin "36") (pinfunction "P1[29]/MCOB2/PCAP1[1]/MAT0[1]_36") (pintype "passive"))
    )
    (net (code "112") (name "unconnected-(U1-P1[30]{slash}VBUS{slash}AD0[4]-Pad18)") (class "Default")
      (node (ref "U1") (pin "18") (pinfunction "P1[30]/VBUS/AD0[4]_18") (pintype "passive"))
    )
    (net (code "113") (name "unconnected-(U1-P1[31]{slash}SCK1{slash}AD0[5]-Pad17)") (class "Default")
      (node (ref "U1") (pin "17") (pinfunction "P1[31]/SCK1/AD0[5]_17") (pintype "passive"))
    )
    (net (code "114") (name "unconnected-(U1-P2[0]{slash}PWM1[1]{slash}TXD1-Pad60)") (class "Default")
      (node (ref "U1") (pin "60") (pinfunction "P2[0]/PWM1[1]/TXD1_60") (pintype "passive"))
    )
    (net (code "115") (name "unconnected-(U1-P2[1]{slash}PWM1[2]{slash}RXD1-Pad59)") (class "Default")
      (node (ref "U1") (pin "59") (pinfunction "P2[1]/PWM1[2]/RXD1_59") (pintype "passive"))
    )
    (net (code "116") (name "unconnected-(U1-P2[3]{slash}PWM1[4]{slash}DCD1{slash}TRACEDATA[2]-Pad55)") (class "Default")
      (node (ref "U1") (pin "55") (pinfunction "P2[3]/PWM1[4]/DCD1/TRACEDATA[2]_55") (pintype "passive"))
    )
    (net (code "117") (name "unconnected-(U1-P2[4]{slash}PWM1[5]{slash}DSR1{slash}TRACEDATA[1]-Pad54)") (class "Default")
      (node (ref "U1") (pin "54") (pinfunction "P2[4]/PWM1[5]/DSR1/TRACEDATA[1]_54") (pintype "passive"))
    )
    (net (code "118") (name "unconnected-(U1-P2[6]{slash}PCAP1[0]{slash}RI1{slash}TRACECLK-Pad52)") (class "Default")
      (node (ref "U1") (pin "52") (pinfunction "P2[6]/PCAP1[0]/RI1/TRACECLK_52") (pintype "passive"))
    )
    (net (code "119") (name "unconnected-(U1-P2[9]{slash}USB_CONNECT{slash}RXD2-Pad49)") (class "Default")
      (node (ref "U1") (pin "49") (pinfunction "P2[9]/USB_CONNECT/RXD2_49") (pintype "passive"))
    )
    (net (code "120") (name "unconnected-(U1-P4[28]{slash}RX_MCLK{slash}MAT2[0]{slash}TXD3-Pad65)") (class "Default")
      (node (ref "U1") (pin "65") (pinfunction "P4[28]/RX_MCLK/MAT2[0]/TXD3_65") (pintype "passive"))
    )
    (net (code "121") (name "unconnected-(U1-P4[29]{slash}TX_MCLK{slash}MAT2[1]{slash}RXD3-Pad68)") (class "Default")
      (node (ref "U1") (pin "68") (pinfunction "P4[29]/TX_MCLK/MAT2[1]/RXD3_68") (pintype "passive"))
    )
    (net (code "122") (name "unconnected-(U1-RTCX1-Pad13)") (class "Default")
      (node (ref "U1") (pin "13") (pinfunction "RTCX1_13") (pintype "passive"))
    )
    (net (code "123") (name "unconnected-(U1-RTCX2-Pad15)") (class "Default")
      (node (ref "U1") (pin "15") (pinfunction "RTCX2_15") (pintype "passive"))
    )
    (net (code "124") (name "unconnected-(U1-TDI-Pad2)") (class "Default")
      (node (ref "U1") (pin "2") (pinfunction "TDI_2") (pintype "passive"))
    )
    (net (code "125") (name "unconnected-(U1-TDO{slash}SWO-Pad1)") (class "Default")
      (node (ref "U1") (pin "1") (pinfunction "TDO/SWO_1") (pintype "passive"))
    )
    (net (code "126") (name "unconnected-(U1-~{RSTOUT}-Pad11)") (class "Default")
      (node (ref "U1") (pin "11") (pinfunction "~{RSTOUT}_11") (pintype "passive"))
    )
    (net (code "127") (name "unconnected-(U1-~{TRST}-Pad4)") (class "Default")
      (node (ref "U1") (pin "4") (pinfunction "~{TRST}_4") (pintype "passive"))
    )
    (net (code "128") (name "unconnected-(U2-SS-Pad8)") (class "Default")
      (node (ref "U2") (pin "8") (pinfunction "SS_8") (pintype "passive"))
    )
    (net (code "129") (name "unconnected-(U7-R2IN-Pad8)") (class "Default")
      (node (ref "U7") (pin "8") (pinfunction "R2IN_8") (pintype "passive"))
    )
    (net (code "130") (name "unconnected-(U7-R2OUT-Pad9)") (class "Default")
      (node (ref "U7") (pin "9") (pinfunction "R2OUT_9") (pintype "passive"))
    )
    (net (code "131") (name "unconnected-(U7-T2IN-Pad10)") (class "Default")
      (node (ref "U7") (pin "10") (pinfunction "T2IN_10") (pintype "passive"))
    )
    (net (code "132") (name "unconnected-(U7-T2OUT-Pad7)") (class "Default")
      (node (ref "U7") (pin "7") (pinfunction "T2OUT_7") (pintype "passive"))
    )
  )
)
